# icm-42688-p.net
KiCad netlist of a schematic drawn in Altium Designer
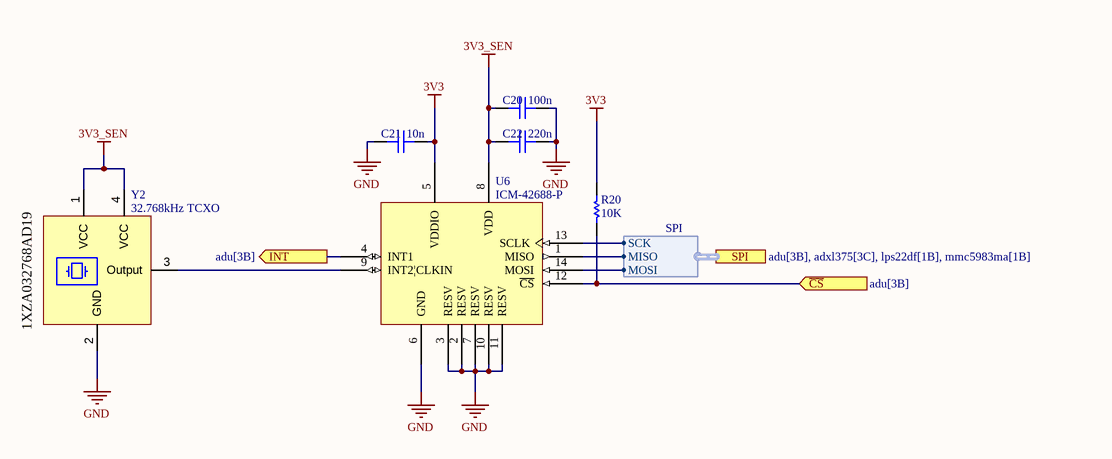
[diagram p0: icm-42688-p.SchDoc]

(export (version "E")
  (design (tool "Eeschema 10.0.6"))
  (components
    (comp (ref "C20")
      (value "100n")
      (footprint "CAP-0603-NP")
      (description "Capacitor")
      (libsource (lib "drfc_schlib") (part "Capacitor"))
    )
    (comp (ref "C21")
      (value "10n")
      (footprint "CAP-0603-NP")
      (description "Capacitor")
      (libsource (lib "drfc_schlib") (part "Capacitor"))
    )
    (comp (ref "C22")
      (value "220n")
      (footprint "CAP-0603-NP")
      (description "Capacitor")
      (libsource (lib "drfc_schlib") (part "Capacitor"))
    )
    (comp (ref "R20")
      (value "10K")
      (footprint "RES-0603")
      (description "Resistor")
      (libsource (lib "drfc_schlib") (part "Resistor"))
    )
    (comp (ref "U6")
      (value "ICM-42688-P")
      (footprint "ICM-42688-P")
      (description "High Precision 6-Axis MEMS Gyro and Accelerometer")
      (libsource (lib "drfc_schlib") (part "ICM-42688-P"))
    )
    (comp (ref "Y2")
      (value "32.768kHz TCXO")
      (footprint "DSK321STD")
      (description "3.3V ±5ppm 32.768kHz SMD3225-4P Temperature Compensated Crystal Oscillators (TCXOs) ROHS")
      (libsource (lib "drfc_schlib") (part "TCXO-4Pin"))
    )
  )
  (nets
    (net (code "2") (name "/INT") (class "Default")
      (node (ref "U6") (pin "4") (pinfunction "INT1_4") (pintype "bidirectional"))
    )
    (net (code "3") (name "/MISO") (class "Default")
      (node (ref "U6") (pin "1") (pinfunction "MISO_1") (pintype "output"))
    )
    (net (code "4") (name "/MOSI") (class "Default")
      (node (ref "U6") (pin "14") (pinfunction "MOSI_14") (pintype "input"))
    )
    (net (code "5") (name "/SCK") (class "Default")
      (node (ref "U6") (pin "13") (pinfunction "SCLK_13") (pintype "input"))
    )
    (net (code "7") (name "/~{CS}") (class "Default")
      (node (ref "R20") (pin "1") (pinfunction "1_1") (pintype "passive"))
      (node (ref "U6") (pin "12") (pinfunction "~{CS}_12") (pintype "input"))
    )
    (net (code "8") (name "3V3") (class "Default")
      (node (ref "C21") (pin "2") (pinfunction "2_2") (pintype "passive"))
      (node (ref "R20") (pin "2") (pinfunction "2_2") (pintype "passive"))
      (node (ref "U6") (pin "5") (pinfunction "VDDIO_5") (pintype "power_in"))
    )
    (net (code "9") (name "3V3_SEN") (class "Default")
      (node (ref "C20") (pin "1") (pinfunction "1_1") (pintype "passive"))
      (node (ref "C22") (pin "1") (pinfunction "1_1") (pintype "passive"))
      (node (ref "U6") (pin "8") (pinfunction "VDD_8") (pintype "power_in"))
      (node (ref "Y2") (pin "1") (pinfunction "VCC_1") (pintype "power_in"))
      (node (ref "Y2") (pin "4") (pinfunction "VCC_4") (pintype "power_in"))
    )
    (net (code "10") (name "GND") (class "Default")
      (node (ref "C20") (pin "2") (pinfunction "2_2") (pintype "passive"))
      (node (ref "C21") (pin "1") (pinfunction "1_1") (pintype "passive"))
      (node (ref "C22") (pin "2") (pinfunction "2_2") (pintype "passive"))
      (node (ref "U6") (pin "10") (pinfunction "RESV_10") (pintype "power_in"))
      (node (ref "U6") (pin "11") (pinfunction "RESV_11") (pintype "power_in"))
      (node (ref "U6") (pin "2") (pinfunction "RESV_2") (pintype "power_in"))
      (node (ref "U6") (pin "3") (pinfunction "RESV_3") (pintype "power_in"))
      (node (ref "U6") (pin "6") (pinfunction "GND_6") (pintype "power_in"))
      (node (ref "U6") (pin "7") (pinfunction "RESV_7") (pintype "power_in"))
      (node (ref "Y2") (pin "2") (pinfunction "GND_2") (pintype "power_in"))
    )
    (net (code "11") (name "Net-(U6-INT2¦CLKIN)") (class "Default")
      (node (ref "U6") (pin "9") (pinfunction "INT2¦CLKIN_9") (pintype "bidirectional"))
      (node (ref "Y2") (pin "3") (pinfunction "Output_3") (pintype "passive"))
    )
  )
)
